# schematic.net
KiCad netlist of a schematic drawn in Altium Designer
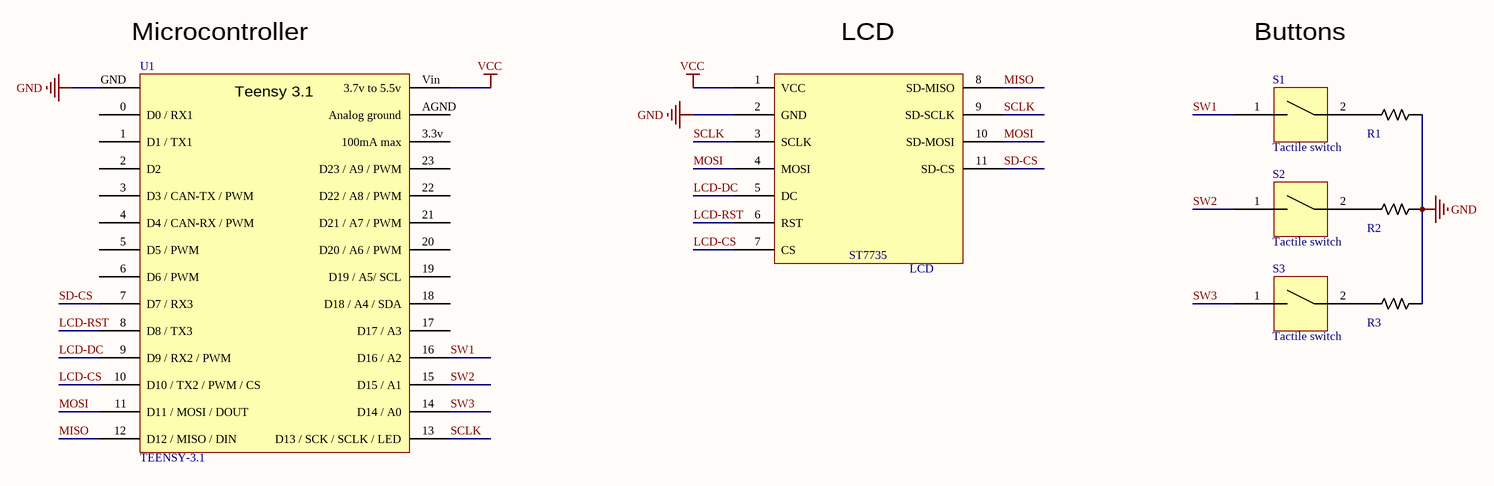
[diagram p0: schematic.SchDoc]

(export (version "E")
  (design (tool "Eeschema 10.0.6"))
  (components
    (comp (ref "LCD1") (value "LCD") (footprint "ST7735") (libsource (lib "custom") (part "ST7735")))
    (comp (ref "R1")
      (value "Resistor")
      (footprint "RESISTOR-0603")
      (libsource (lib "custom") (part "RESISTOR"))
    )
    (comp (ref "R2")
      (value "Resistor")
      (footprint "RESISTOR-0603")
      (libsource (lib "custom") (part "RESISTOR"))
    )
    (comp (ref "R3")
      (value "Resistor")
      (footprint "RESISTOR-0603")
      (libsource (lib "custom") (part "RESISTOR"))
    )
    (comp (ref "S1")
      (value "Tactile switch")
      (footprint "TACTILE-SWITCH")
      (libsource (lib "custom") (part "TACTILE-SWITCH"))
    )
    (comp (ref "S2")
      (value "Tactile switch")
      (footprint "TACTILE-SWITCH")
      (libsource (lib "custom") (part "TACTILE-SWITCH"))
    )
    (comp (ref "S3")
      (value "Tactile switch")
      (footprint "TACTILE-SWITCH")
      (libsource (lib "custom") (part "TACTILE-SWITCH"))
    )
    (comp (ref "U1")
      (value "TEENSY-3.1")
      (footprint "TEENSY-3.1")
      (description "Teensy 3.1 breakout")
      (libsource (lib "custom") (part "TEENSY-3.1"))
    )
  )
  (nets
    (net (code "1") (name "/LCD-CS") (class "Default")
      (node (ref "LCD1") (pin "7") (pinfunction "CS_7") (pintype "passive"))
      (node (ref "U1") (pin "10") (pinfunction "D10_/_TX2_/_PWM_/_CS_10") (pintype "passive"))
    )
    (net (code "2") (name "/LCD-DC") (class "Default")
      (node (ref "LCD1") (pin "5") (pinfunction "DC_5") (pintype "passive"))
      (node (ref "U1") (pin "9") (pinfunction "D9_/_RX2_/_PWM_9") (pintype "passive"))
    )
    (net (code "3") (name "/LCD-RST") (class "Default")
      (node (ref "LCD1") (pin "6") (pinfunction "RST_6") (pintype "passive"))
      (node (ref "U1") (pin "8") (pinfunction "D8_/_TX3_8") (pintype "passive"))
    )
    (net (code "4") (name "/MISO") (class "Default")
      (node (ref "LCD1") (pin "8") (pinfunction "SD-MISO_8") (pintype "passive"))
      (node (ref "U1") (pin "12") (pinfunction "D12_/_MISO_/_DIN_12") (pintype "passive"))
    )
    (net (code "5") (name "/MOSI") (class "Default")
      (node (ref "LCD1") (pin "10") (pinfunction "SD-MOSI_10") (pintype "passive"))
      (node (ref "LCD1") (pin "4") (pinfunction "MOSI_4") (pintype "passive"))
      (node (ref "U1") (pin "11") (pinfunction "D11_/_MOSI_/_DOUT_11") (pintype "passive"))
    )
    (net (code "6") (name "/SCLK") (class "Default")
      (node (ref "LCD1") (pin "3") (pinfunction "SCLK_3") (pintype "passive"))
      (node (ref "LCD1") (pin "9") (pinfunction "SD-SCLK_9") (pintype "passive"))
      (node (ref "U1") (pin "13") (pinfunction "D13_/_SCK_/_SCLK_/_LED_13") (pintype "passive"))
    )
    (net (code "7") (name "/SD-CS") (class "Default")
      (node (ref "LCD1") (pin "11") (pinfunction "SD-CS_11") (pintype "passive"))
      (node (ref "U1") (pin "7") (pinfunction "D7_/_RX3_7") (pintype "passive"))
    )
    (net (code "8") (name "/SW1") (class "Default")
      (node (ref "S1") (pin "1") (pinfunction "1_1") (pintype "passive"))
      (node (ref "U1") (pin "16") (pinfunction "D16_/_A2_16") (pintype "passive"))
    )
    (net (code "9") (name "/SW2") (class "Default")
      (node (ref "S2") (pin "1") (pinfunction "1_1") (pintype "passive"))
      (node (ref "U1") (pin "15") (pinfunction "D15_/_A1_15") (pintype "passive"))
    )
    (net (code "10") (name "/SW3") (class "Default")
      (node (ref "S3") (pin "1") (pinfunction "1_1") (pintype "passive"))
      (node (ref "U1") (pin "14") (pinfunction "D14_/_A0_14") (pintype "passive"))
    )
    (net (code "11") (name "GND") (class "Default")
      (node (ref "LCD1") (pin "2") (pinfunction "GND_2") (pintype "passive"))
      (node (ref "R1") (pin "2") (pinfunction "2_2") (pintype "passive"))
      (node (ref "R2") (pin "2") (pinfunction "2_2") (pintype "passive"))
      (node (ref "R3") (pin "2") (pinfunction "2_2") (pintype "passive"))
      (node (ref "U1") (pin "GND") (pintype "passive"))
    )
    (net (code "12") (name "Net-(R1-Pad1)") (class "Default")
      (node (ref "R1") (pin "1") (pinfunction "1_1") (pintype "passive"))
      (node (ref "S1") (pin "2") (pinfunction "2_2") (pintype "passive"))
    )
    (net (code "13") (name "Net-(R2-Pad1)") (class "Default")
      (node (ref "R2") (pin "1") (pinfunction "1_1") (pintype "passive"))
      (node (ref "S2") (pin "2") (pinfunction "2_2") (pintype "passive"))
    )
    (net (code "14") (name "Net-(R3-Pad1)") (class "Default")
      (node (ref "R3") (pin "1") (pinfunction "1_1") (pintype "passive"))
      (node (ref "S3") (pin "2") (pinfunction "2_2") (pintype "passive"))
    )
    (net (code "15") (name "VCC") (class "Default")
      (node (ref "LCD1") (pin "1") (pinfunction "VCC_1") (pintype "passive"))
      (node (ref "U1") (pin "Vin") (pinfunction "3.7v_to_5.5v_Vin") (pintype "passive"))
    )
    (net (code "16") (name "unconnected-(U1-100mA_max-Pad3.3v)") (class "Default")
      (node (ref "U1") (pin "3.3v") (pinfunction "100mA_max_3.3v") (pintype "passive"))
    )
    (net (code "17") (name "unconnected-(U1-Analog_ground-PadAGND)") (class "Default")
      (node (ref "U1") (pin "AGND") (pinfunction "Analog_ground_AGND") (pintype "passive"))
    )
    (net (code "18") (name "unconnected-(U1-D0_{slash}_RX1-Pad0)") (class "Default")
      (node (ref "U1") (pin "0") (pinfunction "D0_/_RX1_0") (pintype "passive"))
    )
    (net (code "19") (name "unconnected-(U1-D1_{slash}_TX1-Pad1)") (class "Default")
      (node (ref "U1") (pin "1") (pinfunction "D1_/_TX1_1") (pintype "passive"))
    )
    (net (code "20") (name "unconnected-(U1-D2-Pad2)") (class "Default")
      (node (ref "U1") (pin "2") (pinfunction "D2_2") (pintype "passive"))
    )
    (net (code "21") (name "unconnected-(U1-D3_{slash}_CAN-TX_{slash}_PWM-Pad3)") (class "Default")
      (node (ref "U1") (pin "3") (pinfunction "D3_/_CAN-TX_/_PWM_3") (pintype "passive"))
    )
    (net (code "22") (name "unconnected-(U1-D4_{slash}_CAN-RX_{slash}_PWM-Pad4)") (class "Default")
      (node (ref "U1") (pin "4") (pinfunction "D4_/_CAN-RX_/_PWM_4") (pintype "passive"))
    )
    (net (code "23") (name "unconnected-(U1-D5_{slash}_PWM-Pad5)") (class "Default")
      (node (ref "U1") (pin "5") (pinfunction "D5_/_PWM_5") (pintype "passive"))
    )
    (net (code "24") (name "unconnected-(U1-D6_{slash}_PWM-Pad6)") (class "Default")
      (node (ref "U1") (pin "6") (pinfunction "D6_/_PWM_6") (pintype "passive"))
    )
    (net (code "25") (name "unconnected-(U1-D17_{slash}_A3-Pad17)") (class "Default")
      (node (ref "U1") (pin "17") (pinfunction "D17_/_A3_17") (pintype "passive"))
    )
    (net (code "26") (name "unconnected-(U1-D18_{slash}_A4_{slash}_SDA-Pad18)") (class "Default")
      (node (ref "U1") (pin "18") (pinfunction "D18_/_A4_/_SDA_18") (pintype "passive"))
    )
    (net (code "27") (name "unconnected-(U1-D19_{slash}_A5{slash}_SCL-Pad19)") (class "Default")
      (node (ref "U1") (pin "19") (pinfunction "D19_/_A5/_SCL_19") (pintype "passive"))
    )
    (net (code "28") (name "unconnected-(U1-D20_{slash}_A6_{slash}_PWM-Pad20)") (class "Default")
      (node (ref "U1") (pin "20") (pinfunction "D20_/_A6_/_PWM_20") (pintype "passive"))
    )
    (net (code "29") (name "unconnected-(U1-D21_{slash}_A7_{slash}_PWM-Pad21)") (class "Default")
      (node (ref "U1") (pin "21") (pinfunction "D21_/_A7_/_PWM_21") (pintype "passive"))
    )
    (net (code "30") (name "unconnected-(U1-D22_{slash}_A8_{slash}_PWM-Pad22)") (class "Default")
      (node (ref "U1") (pin "22") (pinfunction "D22_/_A8_/_PWM_22") (pintype "passive"))
    )
    (net (code "31") (name "unconnected-(U1-D23_{slash}_A9_{slash}_PWM-Pad23)") (class "Default")
      (node (ref "U1") (pin "23") (pinfunction "D23_/_A9_/_PWM_23") (pintype "passive"))
    )
  )
)
